# Board_Connectors.net
KiCad netlist of a schematic drawn in Altium Designer
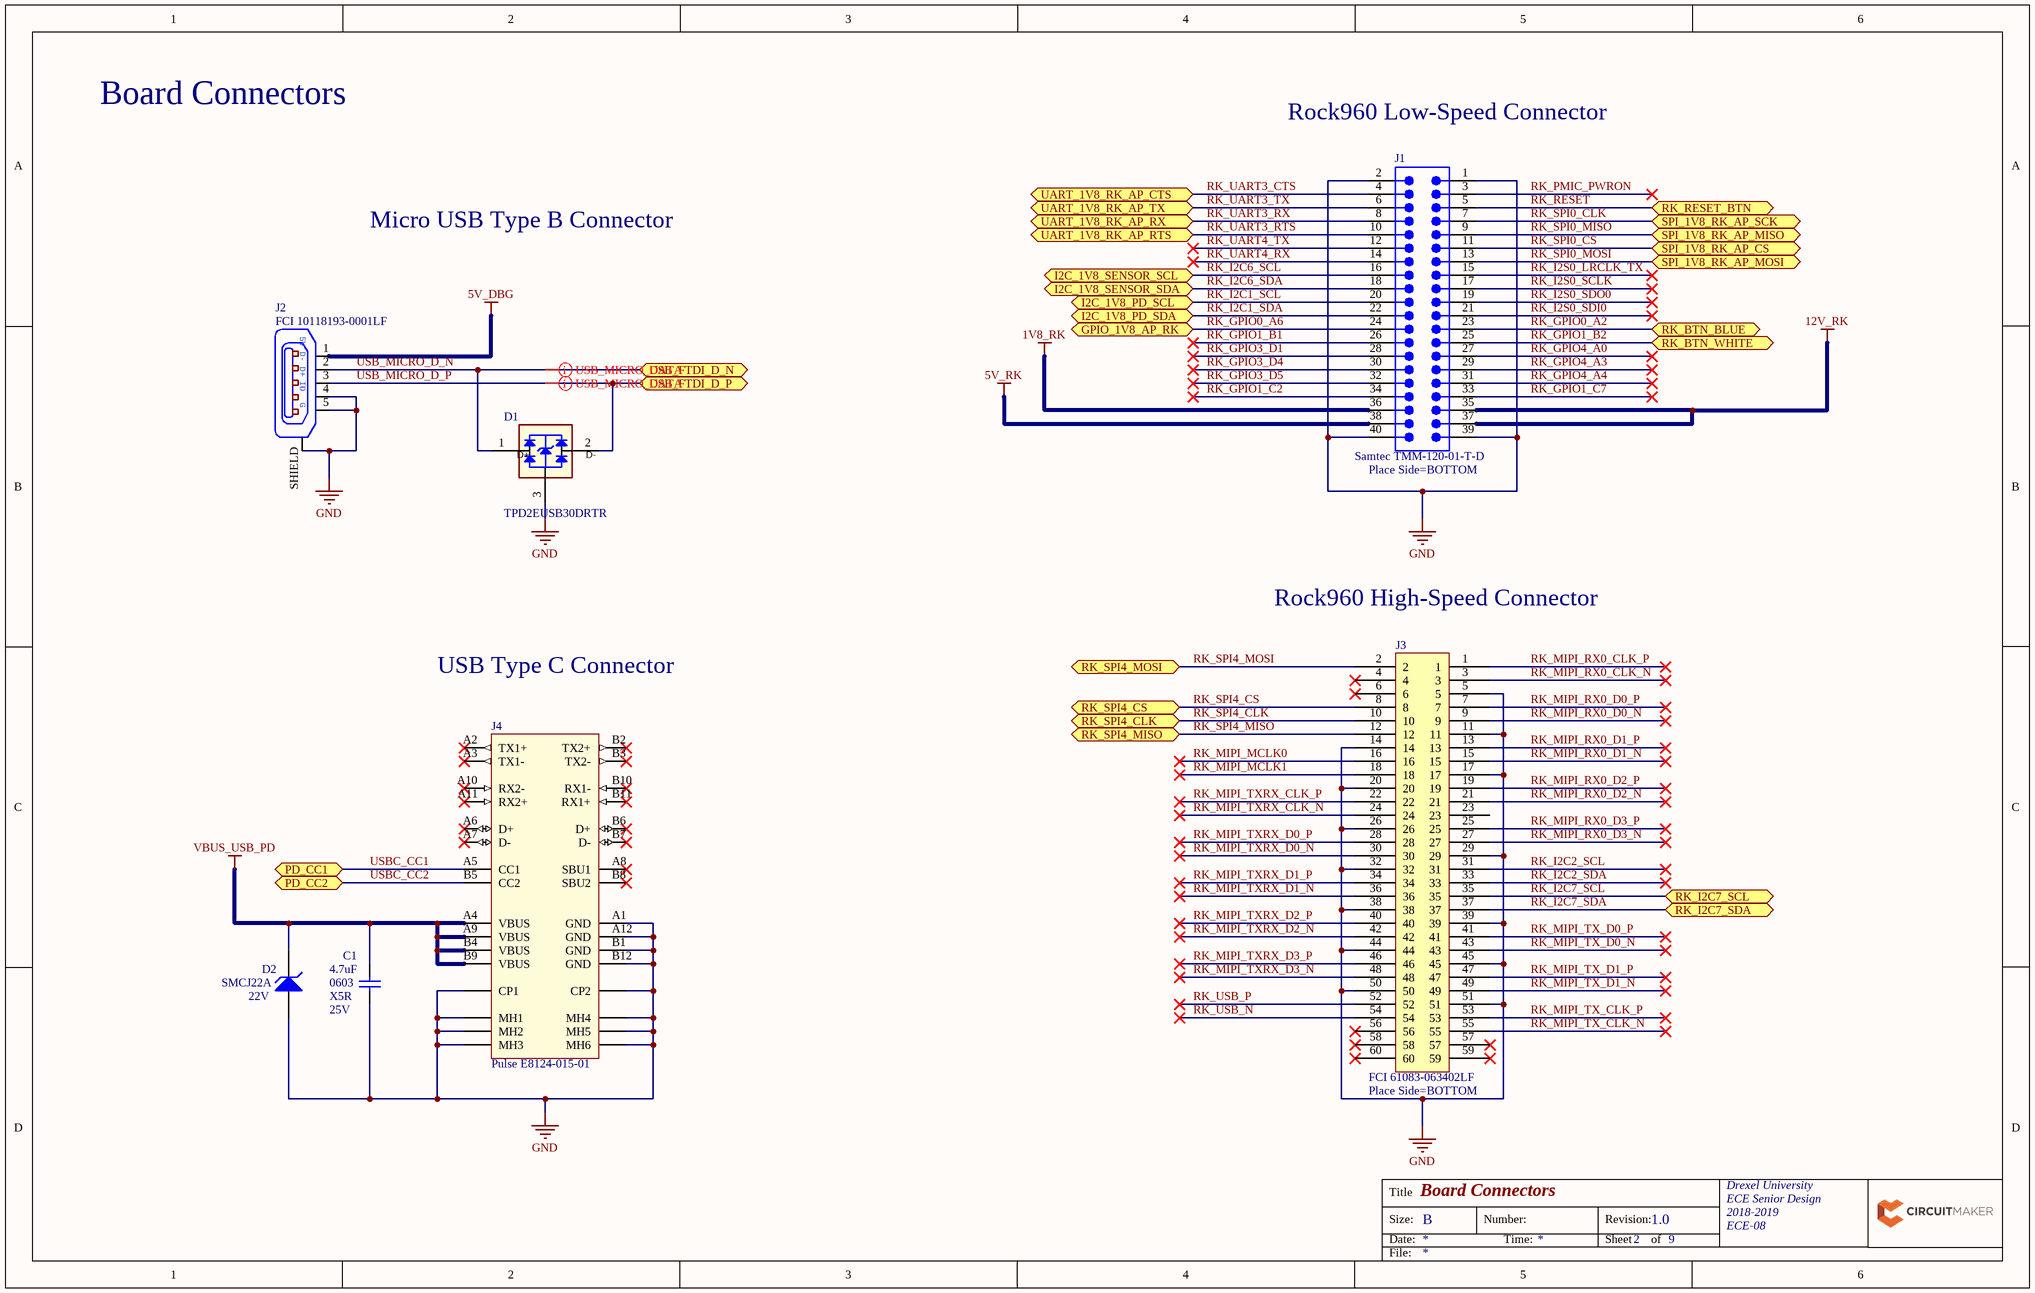
[diagram p0: Board Connectors.SchDoc]

(export (version "E")
  (design (tool "Eeschema 10.0.6"))
  (components
    (comp (ref "C1")
      (value "Murata GRM188R61E475KE11D")
      (footprint "CAPC1608X90X35ML10T15")
      (description "CAP CER 4.7UF 25V 10% X5R 0603")
      (fields
        (field (name "CAPACITANCE") "4.7uF")
        (field (name "CASE/PACKAGE") "0603")
        (field (name "DIELECTRIC CHARACTERISTIC") "X5R")
        (field (name "VOLTAGE RATING (DC)") "25V")
        (field (name "MANUFACTURER PART NUMBER") "GRM188R61E475KE11D")
      )
      (libsource (lib "CommunityVault") (part "CMP-8856396-4"))
    )
    (comp (ref "D1")
      (value "TPD2EUSB30DRTR")
      (footprint "T_TI_TPD2EUSB30DRTR")
      (description "2-Channel ESD Solution for SuperSpeed USB 3.0 Interface 3-SOT -40 to 85")
      (libsource (lib "CommunityVault") (part "CMP-19307392-6"))
    )
    (comp (ref "D2")
      (value "SMCJ22A")
      (footprint "PCB-gk7qhtajnaxh6qo3xtq4-1")
      (description "SMCJ Series 35.5 V 1.5 kW Surface Mount Uni-Directional TVS Diode - DO-214AB")
      (fields (field (name "REVERSE VOLTAGE") "22V"))
      (libsource (lib "CommunityVault") (part "CMP-9cf25530e9434335-1"))
    )
    (comp (ref "J1")
      (value "Samtec TMM-120-01-T-D")
      (footprint "TMM-120-01-T-D")
      (description "Conn Unshrouded Header HDR 40 POS 2mm Solder ST Thru-Hole")
      (fields (field (name "MANUFACTURER PART NUMBER") "TMM-120-01-T-D"))
      (libsource (lib "CommunityVault") (part "CMP-43228a2c51039ce5-1"))
    )
    (comp (ref "J2")
      (value "FCI 10118193-0001LF")
      (footprint "MICRO-USB5+6P-SMD-0.65-B")
      (description "Conn Micro USB Type B RCP 5 POS 0.65mm Solder RA SMD 5 Terminal 1 Port T/R")
      (libsource (lib "CommunityVault") (part "CMP-b7d77f99eeaa6810-17"))
    )
    (comp (ref "J3")
      (value "FCI 61083-063402LF")
      (footprint "PCB-7ti9pzjasutfjj4nekyo-1")
      (description "Bergstak® : 60 Positions; Dual Row; BTBVertical Header tape & Reel")
      (libsource (lib "CommunityVault") (part "CMP-fca037f0475d2367-2"))
    )
    (comp (ref "J4")
      (value "Pulse E8124-015-01")
      (footprint "PCB-zoek8xqsb2swisfr99my-1")
      (description "Conn USB Type C RCP 24 POS 0.5mm Solder RA SMD 24 Terminal 1 Port")
      (libsource (lib "CommunityVault") (part "CMP-5cde91da6a388319-4"))
    )
  )
  (nets
    (net (code "1") (name "/RK_GPIO0_A2") (class "Default")
      (node (ref "J1") (pin "23") (pinfunction "23_23") (pintype "passive"))
    )
    (net (code "2") (name "/RK_GPIO0_A6") (class "Default")
      (node (ref "J1") (pin "24") (pinfunction "24_24") (pintype "passive"))
    )
    (net (code "3") (name "/RK_GPIO1_B1") (class "Default")
      (node (ref "J1") (pin "26") (pinfunction "26_26") (pintype "passive+no_connect"))
    )
    (net (code "4") (name "/RK_GPIO1_B2") (class "Default")
      (node (ref "J1") (pin "25") (pinfunction "25_25") (pintype "passive"))
    )
    (net (code "5") (name "/RK_GPIO1_C2") (class "Default")
      (node (ref "J1") (pin "34") (pinfunction "34_34") (pintype "passive+no_connect"))
    )
    (net (code "6") (name "/RK_GPIO1_C7") (class "Default")
      (node (ref "J1") (pin "33") (pinfunction "33_33") (pintype "passive+no_connect"))
    )
    (net (code "7") (name "/RK_GPIO3_D1") (class "Default")
      (node (ref "J1") (pin "28") (pinfunction "28_28") (pintype "passive+no_connect"))
    )
    (net (code "8") (name "/RK_GPIO3_D4") (class "Default")
      (node (ref "J1") (pin "30") (pinfunction "30_30") (pintype "passive+no_connect"))
    )
    (net (code "9") (name "/RK_GPIO3_D5") (class "Default")
      (node (ref "J1") (pin "32") (pinfunction "32_32") (pintype "passive+no_connect"))
    )
    (net (code "10") (name "/RK_GPIO4_A0") (class "Default")
      (node (ref "J1") (pin "27") (pinfunction "27_27") (pintype "passive+no_connect"))
    )
    (net (code "11") (name "/RK_GPIO4_A3") (class "Default")
      (node (ref "J1") (pin "29") (pinfunction "29_29") (pintype "passive+no_connect"))
    )
    (net (code "12") (name "/RK_GPIO4_A4") (class "Default")
      (node (ref "J1") (pin "31") (pinfunction "31_31") (pintype "passive+no_connect"))
    )
    (net (code "13") (name "/RK_I2C1_SCL") (class "Default")
      (node (ref "J1") (pin "20") (pinfunction "20_20") (pintype "passive"))
    )
    (net (code "14") (name "/RK_I2C1_SDA") (class "Default")
      (node (ref "J1") (pin "22") (pinfunction "22_22") (pintype "passive"))
    )
    (net (code "15") (name "/RK_I2C2_SCL") (class "Default")
      (node (ref "J3") (pin "31") (pinfunction "31_31") (pintype "passive+no_connect"))
    )
    (net (code "16") (name "/RK_I2C2_SDA") (class "Default")
      (node (ref "J3") (pin "33") (pinfunction "33_33") (pintype "passive+no_connect"))
    )
    (net (code "17") (name "/RK_I2C6_SCL") (class "Default")
      (node (ref "J1") (pin "16") (pinfunction "16_16") (pintype "passive"))
    )
    (net (code "18") (name "/RK_I2C6_SDA") (class "Default")
      (node (ref "J1") (pin "18") (pinfunction "18_18") (pintype "passive"))
    )
    (net (code "19") (name "/RK_I2C7_SCL") (class "Default")
      (node (ref "J3") (pin "35") (pinfunction "35_35") (pintype "passive"))
    )
    (net (code "20") (name "/RK_I2C7_SDA") (class "Default")
      (node (ref "J3") (pin "37") (pinfunction "37_37") (pintype "passive"))
    )
    (net (code "21") (name "/RK_I2S0_LRCLK_TX") (class "Default")
      (node (ref "J1") (pin "15") (pinfunction "15_15") (pintype "passive+no_connect"))
    )
    (net (code "22") (name "/RK_I2S0_SCLK") (class "Default")
      (node (ref "J1") (pin "17") (pinfunction "17_17") (pintype "passive+no_connect"))
    )
    (net (code "23") (name "/RK_I2S0_SDI0") (class "Default")
      (node (ref "J1") (pin "21") (pinfunction "21_21") (pintype "passive+no_connect"))
    )
    (net (code "24") (name "/RK_I2S0_SDO0") (class "Default")
      (node (ref "J1") (pin "19") (pinfunction "19_19") (pintype "passive+no_connect"))
    )
    (net (code "25") (name "/RK_MIPI_MCLK0") (class "Default")
      (node (ref "J3") (pin "16") (pinfunction "16_16") (pintype "passive+no_connect"))
    )
    (net (code "26") (name "/RK_MIPI_MCLK1") (class "Default")
      (node (ref "J3") (pin "18") (pinfunction "18_18") (pintype "passive+no_connect"))
    )
    (net (code "27") (name "/RK_MIPI_RX0_CLK_N") (class "Default")
      (node (ref "J3") (pin "3") (pinfunction "3_3") (pintype "passive+no_connect"))
    )
    (net (code "28") (name "/RK_MIPI_RX0_CLK_P") (class "Default")
      (node (ref "J3") (pin "1") (pinfunction "1_1") (pintype "passive+no_connect"))
    )
    (net (code "29") (name "/RK_MIPI_RX0_D0_N") (class "Default")
      (node (ref "J3") (pin "9") (pinfunction "9_9") (pintype "passive+no_connect"))
    )
    (net (code "30") (name "/RK_MIPI_RX0_D0_P") (class "Default")
      (node (ref "J3") (pin "7") (pinfunction "7_7") (pintype "passive+no_connect"))
    )
    (net (code "31") (name "/RK_MIPI_RX0_D1_N") (class "Default")
      (node (ref "J3") (pin "15") (pinfunction "15_15") (pintype "passive+no_connect"))
    )
    (net (code "32") (name "/RK_MIPI_RX0_D1_P") (class "Default")
      (node (ref "J3") (pin "13") (pinfunction "13_13") (pintype "passive+no_connect"))
    )
    (net (code "33") (name "/RK_MIPI_RX0_D2_N") (class "Default")
      (node (ref "J3") (pin "21") (pinfunction "21_21") (pintype "passive+no_connect"))
    )
    (net (code "34") (name "/RK_MIPI_RX0_D2_P") (class "Default")
      (node (ref "J3") (pin "19") (pinfunction "19_19") (pintype "passive+no_connect"))
    )
    (net (code "35") (name "/RK_MIPI_RX0_D3_N") (class "Default")
      (node (ref "J3") (pin "27") (pinfunction "27_27") (pintype "passive+no_connect"))
    )
    (net (code "36") (name "/RK_MIPI_RX0_D3_P") (class "Default")
      (node (ref "J3") (pin "25") (pinfunction "25_25") (pintype "passive+no_connect"))
    )
    (net (code "37") (name "/RK_MIPI_TXRX_CLK_N") (class "Default")
      (node (ref "J3") (pin "24") (pinfunction "24_24") (pintype "passive+no_connect"))
    )
    (net (code "38") (name "/RK_MIPI_TXRX_CLK_P") (class "Default")
      (node (ref "J3") (pin "22") (pinfunction "22_22") (pintype "passive+no_connect"))
    )
    (net (code "39") (name "/RK_MIPI_TXRX_D0_N") (class "Default")
      (node (ref "J3") (pin "30") (pinfunction "30_30") (pintype "passive+no_connect"))
    )
    (net (code "40") (name "/RK_MIPI_TXRX_D0_P") (class "Default")
      (node (ref "J3") (pin "28") (pinfunction "28_28") (pintype "passive+no_connect"))
    )
    (net (code "41") (name "/RK_MIPI_TXRX_D1_N") (class "Default")
      (node (ref "J3") (pin "36") (pinfunction "36_36") (pintype "passive+no_connect"))
    )
    (net (code "42") (name "/RK_MIPI_TXRX_D1_P") (class "Default")
      (node (ref "J3") (pin "34") (pinfunction "34_34") (pintype "passive+no_connect"))
    )
    (net (code "43") (name "/RK_MIPI_TXRX_D2_N") (class "Default")
      (node (ref "J3") (pin "42") (pinfunction "42_42") (pintype "passive+no_connect"))
    )
    (net (code "44") (name "/RK_MIPI_TXRX_D2_P") (class "Default")
      (node (ref "J3") (pin "40") (pinfunction "40_40") (pintype "passive+no_connect"))
    )
    (net (code "45") (name "/RK_MIPI_TXRX_D3_N") (class "Default")
      (node (ref "J3") (pin "48") (pinfunction "48_48") (pintype "passive+no_connect"))
    )
    (net (code "46") (name "/RK_MIPI_TXRX_D3_P") (class "Default")
      (node (ref "J3") (pin "46") (pinfunction "46_46") (pintype "passive+no_connect"))
    )
    (net (code "47") (name "/RK_MIPI_TX_CLK_N") (class "Default")
      (node (ref "J3") (pin "55") (pinfunction "55_55") (pintype "passive+no_connect"))
    )
    (net (code "48") (name "/RK_MIPI_TX_CLK_P") (class "Default")
      (node (ref "J3") (pin "53") (pinfunction "53_53") (pintype "passive+no_connect"))
    )
    (net (code "49") (name "/RK_MIPI_TX_D0_N") (class "Default")
      (node (ref "J3") (pin "43") (pinfunction "43_43") (pintype "passive+no_connect"))
    )
    (net (code "50") (name "/RK_MIPI_TX_D0_P") (class "Default")
      (node (ref "J3") (pin "41") (pinfunction "41_41") (pintype "passive+no_connect"))
    )
    (net (code "51") (name "/RK_MIPI_TX_D1_N") (class "Default")
      (node (ref "J3") (pin "49") (pinfunction "49_49") (pintype "passive+no_connect"))
    )
    (net (code "52") (name "/RK_MIPI_TX_D1_P") (class "Default")
      (node (ref "J3") (pin "47") (pinfunction "47_47") (pintype "passive+no_connect"))
    )
    (net (code "53") (name "/RK_PMIC_PWRON") (class "Default")
      (node (ref "J1") (pin "3") (pinfunction "3_3") (pintype "passive+no_connect"))
    )
    (net (code "54") (name "/RK_RESET") (class "Default")
      (node (ref "J1") (pin "5") (pinfunction "5_5") (pintype "passive"))
    )
    (net (code "55") (name "/RK_SPI0_CLK") (class "Default")
      (node (ref "J1") (pin "7") (pinfunction "7_7") (pintype "passive"))
    )
    (net (code "56") (name "/RK_SPI0_CS") (class "Default")
      (node (ref "J1") (pin "11") (pinfunction "11_11") (pintype "passive"))
    )
    (net (code "57") (name "/RK_SPI0_MISO") (class "Default")
      (node (ref "J1") (pin "9") (pinfunction "9_9") (pintype "passive"))
    )
    (net (code "58") (name "/RK_SPI0_MOSI") (class "Default")
      (node (ref "J1") (pin "13") (pinfunction "13_13") (pintype "passive"))
    )
    (net (code "59") (name "/RK_SPI4_CLK") (class "Default")
      (node (ref "J3") (pin "10") (pinfunction "10_10") (pintype "passive"))
    )
    (net (code "60") (name "/RK_SPI4_CS") (class "Default")
      (node (ref "J3") (pin "8") (pinfunction "8_8") (pintype "passive"))
    )
    (net (code "61") (name "/RK_SPI4_MISO") (class "Default")
      (node (ref "J3") (pin "12") (pinfunction "12_12") (pintype "passive"))
    )
    (net (code "62") (name "/RK_SPI4_MOSI") (class "Default")
      (node (ref "J3") (pin "2") (pinfunction "2_2") (pintype "passive"))
    )
    (net (code "63") (name "/RK_UART3_CTS") (class "Default")
      (node (ref "J1") (pin "4") (pinfunction "4_4") (pintype "passive"))
    )
    (net (code "64") (name "/RK_UART3_RTS") (class "Default")
      (node (ref "J1") (pin "10") (pinfunction "10_10") (pintype "passive"))
    )
    (net (code "65") (name "/RK_UART3_RX") (class "Default")
      (node (ref "J1") (pin "8") (pinfunction "8_8") (pintype "passive"))
    )
    (net (code "66") (name "/RK_UART3_TX") (class "Default")
      (node (ref "J1") (pin "6") (pinfunction "6_6") (pintype "passive"))
    )
    (net (code "67") (name "/RK_UART4_RX") (class "Default")
      (node (ref "J1") (pin "14") (pinfunction "14_14") (pintype "passive+no_connect"))
    )
    (net (code "68") (name "/RK_UART4_TX") (class "Default")
      (node (ref "J1") (pin "12") (pinfunction "12_12") (pintype "passive+no_connect"))
    )
    (net (code "69") (name "/RK_USB_N") (class "Default")
      (node (ref "J3") (pin "54") (pinfunction "54_54") (pintype "passive+no_connect"))
    )
    (net (code "70") (name "/RK_USB_P") (class "Default")
      (node (ref "J3") (pin "52") (pinfunction "52_52") (pintype "passive+no_connect"))
    )
    (net (code "71") (name "/USBC_CC1") (class "Default")
      (node (ref "J4") (pin "A5") (pinfunction "CC1_A5") (pintype "passive"))
    )
    (net (code "72") (name "/USBC_CC2") (class "Default")
      (node (ref "J4") (pin "B5") (pinfunction "CC2_B5") (pintype "passive"))
    )
    (net (code "73") (name "/USB_MICRO_D_N") (class "Default")
      (node (ref "D1") (pin "1") (pinfunction "D+_1") (pintype "power_in"))
      (node (ref "J2") (pin "2") (pinfunction "2_2") (pintype "passive"))
    )
    (net (code "74") (name "/USB_MICRO_D_P") (class "Default")
      (node (ref "D1") (pin "2") (pinfunction "D-_2") (pintype "power_in"))
      (node (ref "J2") (pin "3") (pinfunction "3_3") (pintype "passive"))
    )
    (net (code "75") (name "1V8_RK") (class "Default")
      (node (ref "J1") (pin "36") (pinfunction "36_36") (pintype "passive"))
    )
    (net (code "76") (name "5V_DBG") (class "Default")
      (node (ref "J2") (pin "1") (pinfunction "1_1") (pintype "passive"))
    )
    (net (code "77") (name "5V_RK") (class "Default")
      (node (ref "J1") (pin "38") (pinfunction "38_38") (pintype "passive"))
    )
    (net (code "78") (name "12V_RK") (class "Default")
      (node (ref "J1") (pin "35") (pinfunction "35_35") (pintype "passive"))
      (node (ref "J1") (pin "37") (pinfunction "37_37") (pintype "passive"))
    )
    (net (code "79") (name "GND") (class "Default")
      (node (ref "C1") (pin "1") (pinfunction "1_1") (pintype "passive"))
      (node (ref "D1") (pin "3") (pinfunction "GND_3") (pintype "power_in"))
      (node (ref "D2") (pin "1") (pinfunction "A_1") (pintype "passive"))
      (node (ref "J1") (pin "1") (pinfunction "1_1") (pintype "passive"))
      (node (ref "J1") (pin "2") (pinfunction "2_2") (pintype "passive"))
      (node (ref "J1") (pin "39") (pinfunction "39_39") (pintype "passive"))
      (node (ref "J1") (pin "40") (pinfunction "40_40") (pintype "passive"))
      (node (ref "J2") (pin "4") (pinfunction "4_4") (pintype "passive"))
      (node (ref "J2") (pin "5") (pinfunction "5_5") (pintype "passive"))
      (node (ref "J2") (pin "SHIELD") (pinfunction "6_SHIELD") (pintype "passive"))
      (node (ref "J3") (pin "11") (pinfunction "11_11") (pintype "passive"))
      (node (ref "J3") (pin "14") (pinfunction "14_14") (pintype "passive"))
      (node (ref "J3") (pin "17") (pinfunction "17_17") (pintype "passive"))
      (node (ref "J3") (pin "20") (pinfunction "20_20") (pintype "passive"))
      (node (ref "J3") (pin "26") (pinfunction "26_26") (pintype "passive"))
      (node (ref "J3") (pin "29") (pinfunction "29_29") (pintype "passive"))
      (node (ref "J3") (pin "32") (pinfunction "32_32") (pintype "passive"))
      (node (ref "J3") (pin "38") (pinfunction "38_38") (pintype "passive"))
      (node (ref "J3") (pin "39") (pinfunction "39_39") (pintype "passive"))
      (node (ref "J3") (pin "44") (pinfunction "44_44") (pintype "passive"))
      (node (ref "J3") (pin "45") (pinfunction "45_45") (pintype "passive"))
      (node (ref "J3") (pin "5") (pinfunction "5_5") (pintype "passive"))
      (node (ref "J3") (pin "50") (pinfunction "50_50") (pintype "passive"))
      (node (ref "J3") (pin "51") (pinfunction "51_51") (pintype "passive"))
      (node (ref "J4") (pin "A1") (pinfunction "GND_A1") (pintype "power_in"))
      (node (ref "J4") (pin "A12") (pinfunction "GND_A12") (pintype "power_in"))
      (node (ref "J4") (pin "B1") (pinfunction "GND_B1") (pintype "power_in"))
      (node (ref "J4") (pin "B12") (pinfunction "GND_B12") (pintype "power_in"))
      (node (ref "J4") (pin "CP1") (pinfunction "CP1_CP1") (pintype "passive"))
      (node (ref "J4") (pin "CP2") (pinfunction "CP2_CP2") (pintype "passive"))
      (node (ref "J4") (pin "MH1") (pinfunction "MH1_MH1") (pintype "passive"))
      (node (ref "J4") (pin "MH2") (pinfunction "MH2_MH2") (pintype "passive"))
      (node (ref "J4") (pin "MH3") (pinfunction "MH3_MH3") (pintype "passive"))
      (node (ref "J4") (pin "MH4") (pinfunction "MH4_MH4") (pintype "passive"))
      (node (ref "J4") (pin "MH5") (pinfunction "MH5_MH5") (pintype "passive"))
      (node (ref "J4") (pin "MH6") (pinfunction "MH6_MH6") (pintype "passive"))
    )
    (net (code "80") (name "VBUS_USB_PD") (class "Default")
      (node (ref "C1") (pin "2") (pinfunction "2_2") (pintype "passive"))
      (node (ref "D2") (pin "2") (pinfunction "K_2") (pintype "passive"))
      (node (ref "J4") (pin "A4") (pinfunction "VBUS_A4") (pintype "power_in"))
      (node (ref "J4") (pin "A9") (pinfunction "VBUS_A9") (pintype "power_in"))
      (node (ref "J4") (pin "B4") (pinfunction "VBUS_B4") (pintype "power_in"))
      (node (ref "J4") (pin "B9") (pinfunction "VBUS_B9") (pintype "power_in"))
    )
    (net (code "81") (name "unconnected-(J3-Pad4)") (class "Default")
      (node (ref "J3") (pin "4") (pinfunction "4_4") (pintype "passive+no_connect"))
    )
    (net (code "82") (name "unconnected-(J3-Pad6)") (class "Default")
      (node (ref "J3") (pin "6") (pinfunction "6_6") (pintype "passive+no_connect"))
    )
    (net (code "83") (name "unconnected-(J3-Pad23)") (class "Default")
      (node (ref "J3") (pin "23") (pinfunction "23_23") (pintype "passive"))
    )
    (net (code "84") (name "unconnected-(J3-Pad56)") (class "Default")
      (node (ref "J3") (pin "56") (pinfunction "56_56") (pintype "passive+no_connect"))
    )
    (net (code "85") (name "unconnected-(J3-Pad57)") (class "Default")
      (node (ref "J3") (pin "57") (pinfunction "57_57") (pintype "passive+no_connect"))
    )
    (net (code "86") (name "unconnected-(J3-Pad58)") (class "Default")
      (node (ref "J3") (pin "58") (pinfunction "58_58") (pintype "passive+no_connect"))
    )
    (net (code "87") (name "unconnected-(J3-Pad59)") (class "Default")
      (node (ref "J3") (pin "59") (pinfunction "59_59") (pintype "passive+no_connect"))
    )
    (net (code "88") (name "unconnected-(J3-Pad60)") (class "Default")
      (node (ref "J3") (pin "60") (pinfunction "60_60") (pintype "passive+no_connect"))
    )
    (net (code "89") (name "unconnected-(J4-D+-PadA6)") (class "Default")
      (node (ref "J4") (pin "A6") (pinfunction "D+_A6") (pintype "bidirectional+no_connect"))
    )
    (net (code "90") (name "unconnected-(J4-D+-PadB6)") (class "Default")
      (node (ref "J4") (pin "B6") (pinfunction "D+_B6") (pintype "bidirectional+no_connect"))
    )
    (net (code "91") (name "unconnected-(J4-D--PadA7)") (class "Default")
      (node (ref "J4") (pin "A7") (pinfunction "D-_A7") (pintype "bidirectional+no_connect"))
    )
    (net (code "92") (name "unconnected-(J4-D--PadB7)") (class "Default")
      (node (ref "J4") (pin "B7") (pinfunction "D-_B7") (pintype "bidirectional+no_connect"))
    )
    (net (code "93") (name "unconnected-(J4-RX1+-PadB11)") (class "Default")
      (node (ref "J4") (pin "B11") (pinfunction "RX1+_B11") (pintype "input+no_connect"))
    )
    (net (code "94") (name "unconnected-(J4-RX1--PadB10)") (class "Default")
      (node (ref "J4") (pin "B10") (pinfunction "RX1-_B10") (pintype "input+no_connect"))
    )
    (net (code "95") (name "unconnected-(J4-RX2+-PadA11)") (class "Default")
      (node (ref "J4") (pin "A11") (pinfunction "RX2+_A11") (pintype "input+no_connect"))
    )
    (net (code "96") (name "unconnected-(J4-RX2--PadA10)") (class "Default")
      (node (ref "J4") (pin "A10") (pinfunction "RX2-_A10") (pintype "input+no_connect"))
    )
    (net (code "97") (name "unconnected-(J4-SBU1-PadA8)") (class "Default")
      (node (ref "J4") (pin "A8") (pinfunction "SBU1_A8") (pintype "passive+no_connect"))
    )
    (net (code "98") (name "unconnected-(J4-SBU2-PadB8)") (class "Default")
      (node (ref "J4") (pin "B8") (pinfunction "SBU2_B8") (pintype "passive+no_connect"))
    )
    (net (code "99") (name "unconnected-(J4-TX1+-PadA2)") (class "Default")
      (node (ref "J4") (pin "A2") (pinfunction "TX1+_A2") (pintype "output+no_connect"))
    )
    (net (code "100") (name "unconnected-(J4-TX1--PadA3)") (class "Default")
      (node (ref "J4") (pin "A3") (pinfunction "TX1-_A3") (pintype "output+no_connect"))
    )
    (net (code "101") (name "unconnected-(J4-TX2+-PadB2)") (class "Default")
      (node (ref "J4") (pin "B2") (pinfunction "TX2+_B2") (pintype "output+no_connect"))
    )
    (net (code "102") (name "unconnected-(J4-TX2--PadB3)") (class "Default")
      (node (ref "J4") (pin "B3") (pinfunction "TX2-_B3") (pintype "output+no_connect"))
    )
  )
)
